# CPU_IO_Ports.net
KiCad netlist of a schematic drawn in Altium Designer
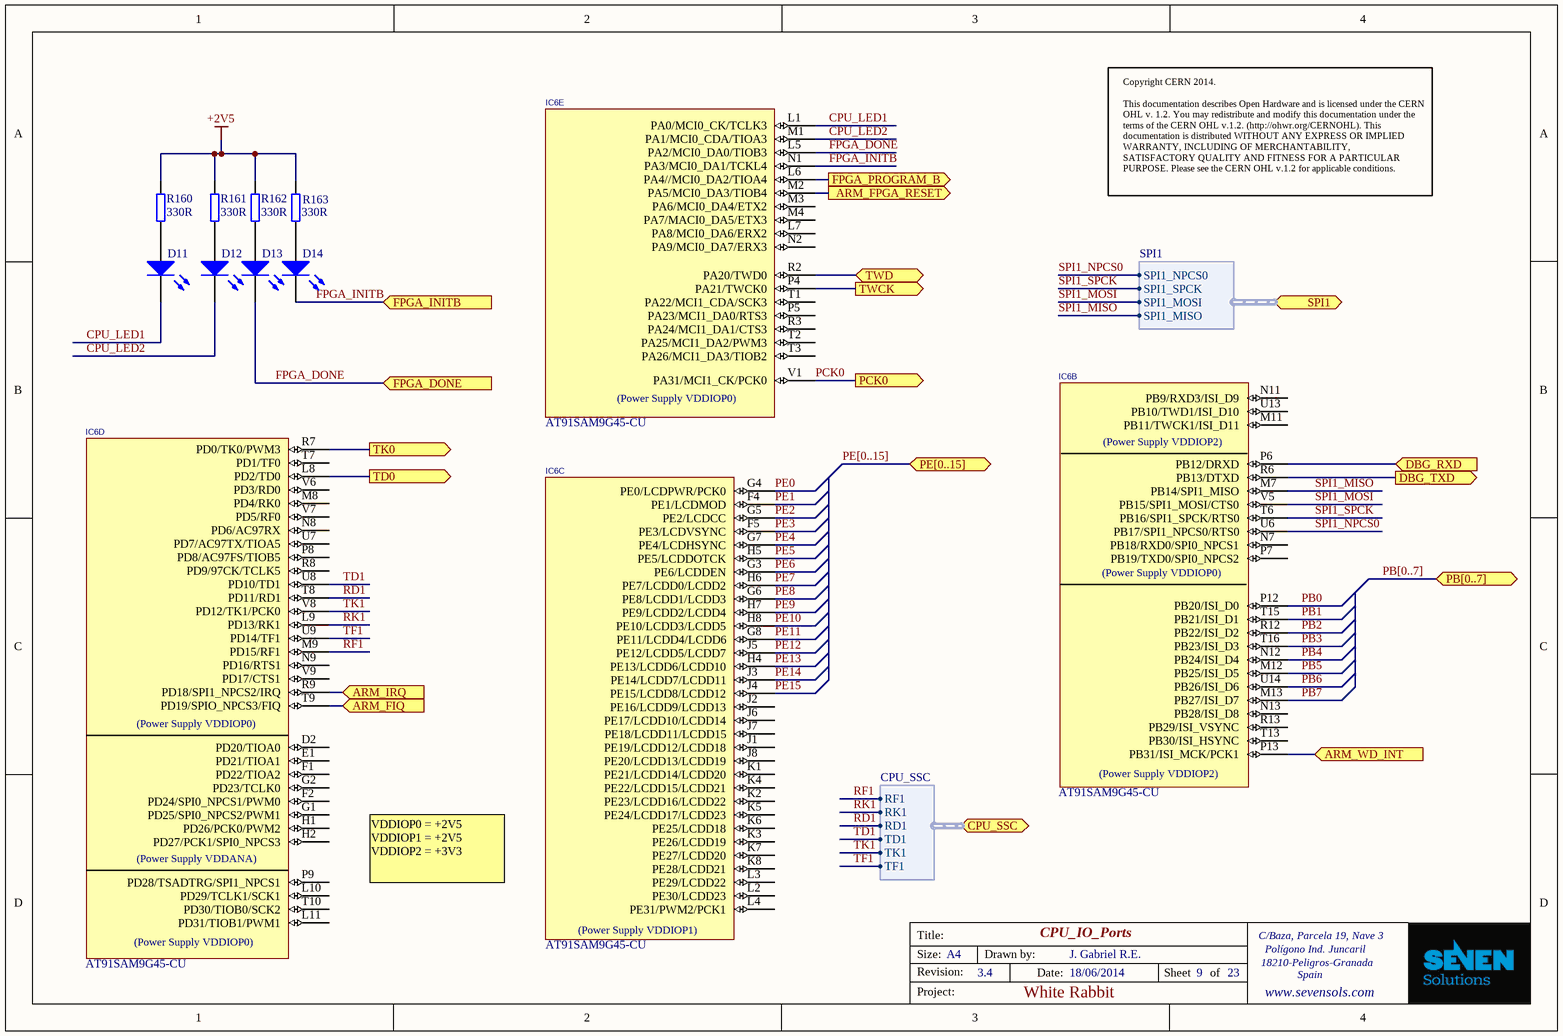
[diagram p0: CPU_IO_Ports.SchDoc]

(export (version "E")
  (design (tool "Eeschema 10.0.6"))
  (components
    (comp (ref "D11")
      (value "LED")
      (footprint "CD1608-0603")
      (description "Typical INFRARED GaAs LED")
      (fields (field (name "PUBLISHER") "Altium Limited"))
      (libsource (lib "wr_switch") (part "LED0"))
    )
    (comp (ref "D12")
      (value "LED")
      (footprint "CD1608-0603")
      (description "Typical INFRARED GaAs LED")
      (fields (field (name "PUBLISHER") "Altium Limited"))
      (libsource (lib "wr_switch") (part "LED0"))
    )
    (comp (ref "D13")
      (value "LED")
      (footprint "CD1608-0603")
      (description "Typical INFRARED GaAs LED")
      (fields (field (name "PUBLISHER") "Altium Limited"))
      (libsource (lib "wr_switch") (part "LED0"))
    )
    (comp (ref "D14")
      (value "LED")
      (footprint "CD1608-0603")
      (description "Typical INFRARED GaAs LED")
      (fields (field (name "PUBLISHER") "Altium Limited"))
      (libsource (lib "wr_switch") (part "LED0"))
    )
    (comp (ref "IC6")
      (value "AT91SAM9G45-CU")
      (footprint "TFBGA324")
      (description "Atmel 400MHz ARM926 MCU")
      (libsource (lib "wr_switch") (part "AT91SAM9G45-CU"))
    )
    (comp (ref "R160")
      (value "330R")
      (footprint "0402")
      (description "SMD Resistor")
      (fields (field (name "TOLERANCE") "±1%"))
      (libsource (lib "wr_switch") (part "RES_SMD"))
    )
    (comp (ref "R161")
      (value "330R")
      (footprint "0402")
      (description "SMD Resistor")
      (fields (field (name "TOLERANCE") "±1%"))
      (libsource (lib "wr_switch") (part "RES_SMD"))
    )
    (comp (ref "R162")
      (value "330R")
      (footprint "0402")
      (description "SMD Resistor")
      (fields (field (name "TOLERANCE") "±1%"))
      (libsource (lib "wr_switch") (part "RES_SMD"))
    )
    (comp (ref "R163")
      (value "330R")
      (footprint "0402")
      (description "SMD Resistor")
      (fields (field (name "TOLERANCE") "±1%"))
      (libsource (lib "wr_switch") (part "RES_SMD"))
    )
  )
  (nets
    (net (code "3") (name "+2V5") (class "Default")
      (node (ref "R160") (pin "2") (pinfunction "2_2") (pintype "passive"))
      (node (ref "R161") (pin "2") (pinfunction "2_2") (pintype "passive"))
      (node (ref "R162") (pin "2") (pinfunction "2_2") (pintype "passive"))
      (node (ref "R163") (pin "2") (pinfunction "2_2") (pintype "passive"))
    )
    (net (code "4") (name "/ARM_FIQ") (class "Default")
      (node (ref "IC6") (pin "T9") (pinfunction "PD19/SPIO_NPCS3/FIQ_T9") (pintype "bidirectional"))
    )
    (net (code "5") (name "/ARM_FPGA_RESET") (class "Default")
      (node (ref "IC6") (pin "M2") (pinfunction "PA5/MCI0_DA3/TIOB4_M2") (pintype "bidirectional"))
    )
    (net (code "6") (name "/ARM_IRQ") (class "Default")
      (node (ref "IC6") (pin "R9") (pinfunction "PD18/SPI1_NPCS2/IRQ_R9") (pintype "bidirectional"))
    )
    (net (code "7") (name "/ARM_WD_INT") (class "Default")
      (node (ref "IC6") (pin "P13") (pinfunction "PB31/ISI_MCK/PCK1_P13") (pintype "bidirectional"))
    )
    (net (code "8") (name "/CPU_LED1") (class "Default")
      (node (ref "D11") (pin "2") (pinfunction "K_2") (pintype "passive"))
      (node (ref "IC6") (pin "L1") (pinfunction "PA0/MCI0_CK/TCLK3_L1") (pintype "bidirectional"))
    )
    (net (code "9") (name "/CPU_LED2") (class "Default")
      (node (ref "D12") (pin "2") (pinfunction "K_2") (pintype "passive"))
      (node (ref "IC6") (pin "M1") (pinfunction "PA1/MCI0_CDA/TIOA3_M1") (pintype "bidirectional"))
    )
    (net (code "10") (name "/DBG_RXD") (class "Default")
      (node (ref "IC6") (pin "P6") (pinfunction "PB12/DRXD_P6") (pintype "bidirectional"))
    )
    (net (code "11") (name "/DBG_TXD") (class "Default")
      (node (ref "IC6") (pin "R6") (pinfunction "PB13/DTXD_R6") (pintype "bidirectional"))
    )
    (net (code "12") (name "/FPGA_DONE") (class "Default")
      (node (ref "D13") (pin "2") (pinfunction "K_2") (pintype "passive"))
      (node (ref "IC6") (pin "L5") (pinfunction "PA2/MCI0_DA0/TIOB3_L5") (pintype "bidirectional"))
    )
    (net (code "13") (name "/FPGA_INITB") (class "Default")
      (node (ref "D14") (pin "2") (pinfunction "K_2") (pintype "passive"))
      (node (ref "IC6") (pin "N1") (pinfunction "PA3/MCI0_DA1/TCKL4_N1") (pintype "bidirectional"))
    )
    (net (code "14") (name "/FPGA_PROGRAM_B") (class "Default")
      (node (ref "IC6") (pin "L6") (pinfunction "PA4//MCI0_DA2/TIOA4_L6") (pintype "bidirectional"))
    )
    (net (code "15") (name "/PB0") (class "Default")
      (node (ref "IC6") (pin "P12") (pinfunction "PB20/ISI_D0_P12") (pintype "bidirectional"))
    )
    (net (code "16") (name "/PB1") (class "Default")
      (node (ref "IC6") (pin "T15") (pinfunction "PB21/ISI_D1_T15") (pintype "bidirectional"))
    )
    (net (code "17") (name "/PB2") (class "Default")
      (node (ref "IC6") (pin "R12") (pinfunction "PB22/ISI_D2_R12") (pintype "bidirectional"))
    )
    (net (code "18") (name "/PB3") (class "Default")
      (node (ref "IC6") (pin "T16") (pinfunction "PB23/ISI_D3_T16") (pintype "bidirectional"))
    )
    (net (code "19") (name "/PB4") (class "Default")
      (node (ref "IC6") (pin "N12") (pinfunction "PB24/ISI_D4_N12") (pintype "bidirectional"))
    )
    (net (code "20") (name "/PB5") (class "Default")
      (node (ref "IC6") (pin "M12") (pinfunction "PB25/ISI_D5_M12") (pintype "bidirectional"))
    )
    (net (code "21") (name "/PB6") (class "Default")
      (node (ref "IC6") (pin "U14") (pinfunction "PB26/ISI_D6_U14") (pintype "bidirectional"))
    )
    (net (code "22") (name "/PB7") (class "Default")
      (node (ref "IC6") (pin "M13") (pinfunction "PB27/ISI_D7_M13") (pintype "bidirectional"))
    )
    (net (code "24") (name "/PCK0") (class "Default")
      (node (ref "IC6") (pin "V1") (pinfunction "PA31/MCI1_CK/PCK0_V1") (pintype "bidirectional"))
    )
    (net (code "25") (name "/PE0") (class "Default")
      (node (ref "IC6") (pin "G4") (pinfunction "PE0/LCDPWR/PCK0_G4") (pintype "bidirectional"))
    )
    (net (code "26") (name "/PE1") (class "Default")
      (node (ref "IC6") (pin "F4") (pinfunction "PE1/LCDMOD_F4") (pintype "bidirectional"))
    )
    (net (code "27") (name "/PE2") (class "Default")
      (node (ref "IC6") (pin "G5") (pinfunction "PE2/LCDCC_G5") (pintype "bidirectional"))
    )
    (net (code "28") (name "/PE3") (class "Default")
      (node (ref "IC6") (pin "F5") (pinfunction "PE3/LCDVSYNC_F5") (pintype "bidirectional"))
    )
    (net (code "29") (name "/PE4") (class "Default")
      (node (ref "IC6") (pin "G7") (pinfunction "PE4/LCDHSYNC_G7") (pintype "bidirectional"))
    )
    (net (code "30") (name "/PE5") (class "Default")
      (node (ref "IC6") (pin "H5") (pinfunction "PE5/LCDDOTCK_H5") (pintype "bidirectional"))
    )
    (net (code "31") (name "/PE6") (class "Default")
      (node (ref "IC6") (pin "G3") (pinfunction "PE6/LCDDEN_G3") (pintype "bidirectional"))
    )
    (net (code "32") (name "/PE7") (class "Default")
      (node (ref "IC6") (pin "H6") (pinfunction "PE7/LCDD0/LCDD2_H6") (pintype "bidirectional"))
    )
    (net (code "33") (name "/PE8") (class "Default")
      (node (ref "IC6") (pin "G6") (pinfunction "PE8/LCDD1/LCDD3_G6") (pintype "bidirectional"))
    )
    (net (code "34") (name "/PE9") (class "Default")
      (node (ref "IC6") (pin "H7") (pinfunction "PE9/LCDD2/LCDD4_H7") (pintype "bidirectional"))
    )
    (net (code "35") (name "/PE10") (class "Default")
      (node (ref "IC6") (pin "H8") (pinfunction "PE10/LCDD3/LCDD5_H8") (pintype "bidirectional"))
    )
    (net (code "36") (name "/PE11") (class "Default")
      (node (ref "IC6") (pin "G8") (pinfunction "PE11/LCDD4/LCDD6_G8") (pintype "bidirectional"))
    )
    (net (code "37") (name "/PE12") (class "Default")
      (node (ref "IC6") (pin "J5") (pinfunction "PE12/LCDD5/LCDD7_J5") (pintype "bidirectional"))
    )
    (net (code "38") (name "/PE13") (class "Default")
      (node (ref "IC6") (pin "H4") (pinfunction "PE13/LCDD6/LCDD10_H4") (pintype "bidirectional"))
    )
    (net (code "39") (name "/PE14") (class "Default")
      (node (ref "IC6") (pin "J3") (pinfunction "PE14/LCDD7/LCDD11_J3") (pintype "bidirectional"))
    )
    (net (code "40") (name "/PE15") (class "Default")
      (node (ref "IC6") (pin "J4") (pinfunction "PE15/LCDD8/LCDD12_J4") (pintype "bidirectional"))
    )
    (net (code "42") (name "/RD1") (class "Default")
      (node (ref "IC6") (pin "T8") (pinfunction "PD11/RD1_T8") (pintype "bidirectional"))
    )
    (net (code "43") (name "/RF1") (class "Default")
      (node (ref "IC6") (pin "M9") (pinfunction "PD15/RF1_M9") (pintype "bidirectional"))
    )
    (net (code "44") (name "/RK1") (class "Default")
      (node (ref "IC6") (pin "L9") (pinfunction "PD13/RK1_L9") (pintype "bidirectional"))
    )
    (net (code "45") (name "/SPI1_MISO") (class "Default")
      (node (ref "IC6") (pin "M7") (pinfunction "PB14/SPI1_MISO_M7") (pintype "bidirectional"))
    )
    (net (code "46") (name "/SPI1_MOSI") (class "Default")
      (node (ref "IC6") (pin "V5") (pinfunction "PB15/SPI1_MOSI/CTS0_V5") (pintype "bidirectional"))
    )
    (net (code "47") (name "/SPI1_NPCS0") (class "Default")
      (node (ref "IC6") (pin "U6") (pinfunction "PB17/SPI1_NPCS0/RTS0_U6") (pintype "bidirectional"))
    )
    (net (code "48") (name "/SPI1_SPCK") (class "Default")
      (node (ref "IC6") (pin "T6") (pinfunction "PB16/SPI1_SPCK/RTS0_T6") (pintype "bidirectional"))
    )
    (net (code "49") (name "/TD0") (class "Default")
      (node (ref "IC6") (pin "L8") (pinfunction "PD2/TD0_L8") (pintype "bidirectional"))
    )
    (net (code "50") (name "/TD1") (class "Default")
      (node (ref "IC6") (pin "U8") (pinfunction "PD10/TD1_U8") (pintype "bidirectional"))
    )
    (net (code "51") (name "/TF1") (class "Default")
      (node (ref "IC6") (pin "U9") (pinfunction "PD14/TF1_U9") (pintype "bidirectional"))
    )
    (net (code "52") (name "/TK0") (class "Default")
      (node (ref "IC6") (pin "R7") (pinfunction "PD0/TK0/PWM3_R7") (pintype "bidirectional"))
    )
    (net (code "53") (name "/TK1") (class "Default")
      (node (ref "IC6") (pin "V8") (pinfunction "PD12/TK1/PCK0_V8") (pintype "bidirectional"))
    )
    (net (code "54") (name "/TWCK") (class "Default")
      (node (ref "IC6") (pin "P4") (pinfunction "PA21/TWCK0_P4") (pintype "bidirectional"))
    )
    (net (code "55") (name "/TWD") (class "Default")
      (node (ref "IC6") (pin "R2") (pinfunction "PA20/TWD0_R2") (pintype "bidirectional"))
    )
    (net (code "58") (name "Net-(D11-A)") (class "Default")
      (node (ref "D11") (pin "1") (pinfunction "A_1") (pintype "passive"))
      (node (ref "R160") (pin "1") (pinfunction "1_1") (pintype "passive"))
    )
    (net (code "59") (name "Net-(D12-A)") (class "Default")
      (node (ref "D12") (pin "1") (pinfunction "A_1") (pintype "passive"))
      (node (ref "R161") (pin "1") (pinfunction "1_1") (pintype "passive"))
    )
    (net (code "60") (name "Net-(D13-A)") (class "Default")
      (node (ref "D13") (pin "1") (pinfunction "A_1") (pintype "passive"))
      (node (ref "R162") (pin "1") (pinfunction "1_1") (pintype "passive"))
    )
    (net (code "61") (name "Net-(D14-A)") (class "Default")
      (node (ref "D14") (pin "1") (pinfunction "A_1") (pintype "passive"))
      (node (ref "R163") (pin "1") (pinfunction "1_1") (pintype "passive"))
    )
    (net (code "62") (name "unconnected-(IC6B-PB9{slash}RXD3{slash}ISI_D9-PadN11)") (class "Default")
      (node (ref "IC6") (pin "N11") (pinfunction "PB9/RXD3/ISI_D9_N11") (pintype "bidirectional"))
    )
    (net (code "63") (name "unconnected-(IC6B-PB10{slash}TWD1{slash}ISI_D10-PadU13)") (class "Default")
      (node (ref "IC6") (pin "U13") (pinfunction "PB10/TWD1/ISI_D10_U13") (pintype "bidirectional"))
    )
    (net (code "64") (name "unconnected-(IC6B-PB11{slash}TWCK1{slash}ISI_D11-PadM11)") (class "Default")
      (node (ref "IC6") (pin "M11") (pinfunction "PB11/TWCK1/ISI_D11_M11") (pintype "bidirectional"))
    )
    (net (code "65") (name "unconnected-(IC6B-PB18{slash}RXD0{slash}SPI0_NPCS1-PadN7)") (class "Default")
      (node (ref "IC6") (pin "N7") (pinfunction "PB18/RXD0/SPI0_NPCS1_N7") (pintype "bidirectional"))
    )
    (net (code "66") (name "unconnected-(IC6B-PB19{slash}TXD0{slash}SPI0_NPCS2-PadP7)") (class "Default")
      (node (ref "IC6") (pin "P7") (pinfunction "PB19/TXD0/SPI0_NPCS2_P7") (pintype "bidirectional"))
    )
    (net (code "67") (name "unconnected-(IC6B-PB28{slash}ISI_D8-PadN13)") (class "Default")
      (node (ref "IC6") (pin "N13") (pinfunction "PB28/ISI_D8_N13") (pintype "bidirectional"))
    )
    (net (code "68") (name "unconnected-(IC6B-PB29{slash}ISI_VSYNC-PadR13)") (class "Default")
      (node (ref "IC6") (pin "R13") (pinfunction "PB29/ISI_VSYNC_R13") (pintype "bidirectional"))
    )
    (net (code "69") (name "unconnected-(IC6B-PB30{slash}ISI_HSYNC-PadT13)") (class "Default")
      (node (ref "IC6") (pin "T13") (pinfunction "PB30/ISI_HSYNC_T13") (pintype "bidirectional"))
    )
    (net (code "70") (name "unconnected-(IC6C-PE16{slash}LCDD9{slash}LCDD13-PadJ2)") (class "Default")
      (node (ref "IC6") (pin "J2") (pinfunction "PE16/LCDD9/LCDD13_J2") (pintype "bidirectional"))
    )
    (net (code "71") (name "unconnected-(IC6C-PE17{slash}LCDD10{slash}LCDD14-PadJ6)") (class "Default")
      (node (ref "IC6") (pin "J6") (pinfunction "PE17/LCDD10/LCDD14_J6") (pintype "bidirectional"))
    )
    (net (code "72") (name "unconnected-(IC6C-PE18{slash}LCDD11{slash}LCDD15-PadJ7)") (class "Default")
      (node (ref "IC6") (pin "J7") (pinfunction "PE18/LCDD11/LCDD15_J7") (pintype "bidirectional"))
    )
    (net (code "73") (name "unconnected-(IC6C-PE19{slash}LCDD12{slash}LCDD18-PadJ1)") (class "Default")
      (node (ref "IC6") (pin "J1") (pinfunction "PE19/LCDD12/LCDD18_J1") (pintype "bidirectional"))
    )
    (net (code "74") (name "unconnected-(IC6C-PE20{slash}LCDD13{slash}LCDD19-PadJ8)") (class "Default")
      (node (ref "IC6") (pin "J8") (pinfunction "PE20/LCDD13/LCDD19_J8") (pintype "bidirectional"))
    )
    (net (code "75") (name "unconnected-(IC6C-PE21{slash}LCDD14{slash}LCDD20-PadK1)") (class "Default")
      (node (ref "IC6") (pin "K1") (pinfunction "PE21/LCDD14/LCDD20_K1") (pintype "bidirectional"))
    )
    (net (code "76") (name "unconnected-(IC6C-PE22{slash}LCDD15{slash}LCDD21-PadK4)") (class "Default")
      (node (ref "IC6") (pin "K4") (pinfunction "PE22/LCDD15/LCDD21_K4") (pintype "bidirectional"))
    )
    (net (code "77") (name "unconnected-(IC6C-PE23{slash}LCDD16{slash}LCDD22-PadK2)") (class "Default")
      (node (ref "IC6") (pin "K2") (pinfunction "PE23/LCDD16/LCDD22_K2") (pintype "bidirectional"))
    )
    (net (code "78") (name "unconnected-(IC6C-PE24{slash}LCDD17{slash}LCDD23-PadK5)") (class "Default")
      (node (ref "IC6") (pin "K5") (pinfunction "PE24/LCDD17/LCDD23_K5") (pintype "bidirectional"))
    )
    (net (code "79") (name "unconnected-(IC6C-PE25{slash}LCDD18-PadK6)") (class "Default")
      (node (ref "IC6") (pin "K6") (pinfunction "PE25/LCDD18_K6") (pintype "bidirectional"))
    )
    (net (code "80") (name "unconnected-(IC6C-PE26{slash}LCDD19-PadK3)") (class "Default")
      (node (ref "IC6") (pin "K3") (pinfunction "PE26/LCDD19_K3") (pintype "bidirectional"))
    )
    (net (code "81") (name "unconnected-(IC6C-PE27{slash}LCDD20-PadK7)") (class "Default")
      (node (ref "IC6") (pin "K7") (pinfunction "PE27/LCDD20_K7") (pintype "bidirectional"))
    )
    (net (code "82") (name "unconnected-(IC6C-PE28{slash}LCDD21-PadK8)") (class "Default")
      (node (ref "IC6") (pin "K8") (pinfunction "PE28/LCDD21_K8") (pintype "bidirectional"))
    )
    (net (code "83") (name "unconnected-(IC6C-PE29{slash}LCDD22-PadL3)") (class "Default")
      (node (ref "IC6") (pin "L3") (pinfunction "PE29/LCDD22_L3") (pintype "bidirectional"))
    )
    (net (code "84") (name "unconnected-(IC6C-PE30{slash}LCDD23-PadL2)") (class "Default")
      (node (ref "IC6") (pin "L2") (pinfunction "PE30/LCDD23_L2") (pintype "bidirectional"))
    )
    (net (code "85") (name "unconnected-(IC6C-PE31{slash}PWM2{slash}PCK1-PadL4)") (class "Default")
      (node (ref "IC6") (pin "L4") (pinfunction "PE31/PWM2/PCK1_L4") (pintype "bidirectional"))
    )
    (net (code "86") (name "unconnected-(IC6D-PD1{slash}TF0-PadT7)") (class "Default")
      (node (ref "IC6") (pin "T7") (pinfunction "PD1/TF0_T7") (pintype "bidirectional"))
    )
    (net (code "87") (name "unconnected-(IC6D-PD3{slash}RD0-PadV6)") (class "Default")
      (node (ref "IC6") (pin "V6") (pinfunction "PD3/RD0_V6") (pintype "bidirectional"))
    )
    (net (code "88") (name "unconnected-(IC6D-PD4{slash}RK0-PadM8)") (class "Default")
      (node (ref "IC6") (pin "M8") (pinfunction "PD4/RK0_M8") (pintype "bidirectional"))
    )
    (net (code "89") (name "unconnected-(IC6D-PD5{slash}RF0-PadV7)") (class "Default")
      (node (ref "IC6") (pin "V7") (pinfunction "PD5/RF0_V7") (pintype "bidirectional"))
    )
    (net (code "90") (name "unconnected-(IC6D-PD6{slash}AC97RX-PadN8)") (class "Default")
      (node (ref "IC6") (pin "N8") (pinfunction "PD6/AC97RX_N8") (pintype "bidirectional"))
    )
    (net (code "91") (name "unconnected-(IC6D-PD7{slash}AC97TX{slash}TIOA5-PadU7)") (class "Default")
      (node (ref "IC6") (pin "U7") (pinfunction "PD7/AC97TX/TIOA5_U7") (pintype "bidirectional"))
    )
    (net (code "92") (name "unconnected-(IC6D-PD8{slash}AC97FS{slash}TIOB5-PadP8)") (class "Default")
      (node (ref "IC6") (pin "P8") (pinfunction "PD8/AC97FS/TIOB5_P8") (pintype "bidirectional"))
    )
    (net (code "93") (name "unconnected-(IC6D-PD9{slash}97CK{slash}TCLK5-PadR8)") (class "Default")
      (node (ref "IC6") (pin "R8") (pinfunction "PD9/97CK/TCLK5_R8") (pintype "bidirectional"))
    )
    (net (code "94") (name "unconnected-(IC6D-PD16{slash}RTS1-PadN9)") (class "Default")
      (node (ref "IC6") (pin "N9") (pinfunction "PD16/RTS1_N9") (pintype "bidirectional"))
    )
    (net (code "95") (name "unconnected-(IC6D-PD17{slash}CTS1-PadV9)") (class "Default")
      (node (ref "IC6") (pin "V9") (pinfunction "PD17/CTS1_V9") (pintype "bidirectional"))
    )
    (net (code "96") (name "unconnected-(IC6D-PD20{slash}TIOA0-PadD2)") (class "Default")
      (node (ref "IC6") (pin "D2") (pinfunction "PD20/TIOA0_D2") (pintype "bidirectional"))
    )
    (net (code "97") (name "unconnected-(IC6D-PD21{slash}TIOA1-PadE1)") (class "Default")
      (node (ref "IC6") (pin "E1") (pinfunction "PD21/TIOA1_E1") (pintype "bidirectional"))
    )
    (net (code "98") (name "unconnected-(IC6D-PD22{slash}TIOA2-PadF1)") (class "Default")
      (node (ref "IC6") (pin "F1") (pinfunction "PD22/TIOA2_F1") (pintype "bidirectional"))
    )
    (net (code "99") (name "unconnected-(IC6D-PD23{slash}TCLK0-PadG2)") (class "Default")
      (node (ref "IC6") (pin "G2") (pinfunction "PD23/TCLK0_G2") (pintype "bidirectional"))
    )
    (net (code "100") (name "unconnected-(IC6D-PD24{slash}SPI0_NPCS1{slash}PWM0-PadF2)") (class "Default")
      (node (ref "IC6") (pin "F2") (pinfunction "PD24/SPI0_NPCS1/PWM0_F2") (pintype "bidirectional"))
    )
    (net (code "101") (name "unconnected-(IC6D-PD25{slash}SPI0_NPCS2{slash}PWM1-PadG1)") (class "Default")
      (node (ref "IC6") (pin "G1") (pinfunction "PD25/SPI0_NPCS2/PWM1_G1") (pintype "bidirectional"))
    )
    (net (code "102") (name "unconnected-(IC6D-PD26{slash}PCK0{slash}PWM2-PadH1)") (class "Default")
      (node (ref "IC6") (pin "H1") (pinfunction "PD26/PCK0/PWM2_H1") (pintype "bidirectional"))
    )
    (net (code "103") (name "unconnected-(IC6D-PD27{slash}PCK1{slash}SPI0_NPCS3-PadH2)") (class "Default")
      (node (ref "IC6") (pin "H2") (pinfunction "PD27/PCK1/SPI0_NPCS3_H2") (pintype "bidirectional"))
    )
    (net (code "104") (name "unconnected-(IC6D-PD28{slash}TSADTRG{slash}SPI1_NPCS1-PadP9)") (class "Default")
      (node (ref "IC6") (pin "P9") (pinfunction "PD28/TSADTRG/SPI1_NPCS1_P9") (pintype "bidirectional"))
    )
    (net (code "105") (name "unconnected-(IC6D-PD29{slash}TCLK1{slash}SCK1-PadL10)") (class "Default")
      (node (ref "IC6") (pin "L10") (pinfunction "PD29/TCLK1/SCK1_L10") (pintype "bidirectional"))
    )
    (net (code "106") (name "unconnected-(IC6D-PD30{slash}TIOB0{slash}SCK2-PadT10)") (class "Default")
      (node (ref "IC6") (pin "T10") (pinfunction "PD30/TIOB0/SCK2_T10") (pintype "bidirectional"))
    )
    (net (code "107") (name "unconnected-(IC6D-PD31{slash}TIOB1{slash}PWM1-PadL11)") (class "Default")
      (node (ref "IC6") (pin "L11") (pinfunction "PD31/TIOB1/PWM1_L11") (pintype "bidirectional"))
    )
    (net (code "108") (name "unconnected-(IC6E-PA6{slash}MCI0_DA4{slash}ETX2-PadM3)") (class "Default")
      (node (ref "IC6") (pin "M3") (pinfunction "PA6/MCI0_DA4/ETX2_M3") (pintype "bidirectional"))
    )
    (net (code "109") (name "unconnected-(IC6E-PA7{slash}MACI0_DA5{slash}ETX3-PadM4)") (class "Default")
      (node (ref "IC6") (pin "M4") (pinfunction "PA7/MACI0_DA5/ETX3_M4") (pintype "bidirectional"))
    )
    (net (code "110") (name "unconnected-(IC6E-PA8{slash}MCI0_DA6{slash}ERX2-PadL7)") (class "Default")
      (node (ref "IC6") (pin "L7") (pinfunction "PA8/MCI0_DA6/ERX2_L7") (pintype "bidirectional"))
    )
    (net (code "111") (name "unconnected-(IC6E-PA9{slash}MCI0_DA7{slash}ERX3-PadN2)") (class "Default")
      (node (ref "IC6") (pin "N2") (pinfunction "PA9/MCI0_DA7/ERX3_N2") (pintype "bidirectional"))
    )
    (net (code "112") (name "unconnected-(IC6E-PA22{slash}MCI1_CDA{slash}SCK3-PadT1)") (class "Default")
      (node (ref "IC6") (pin "T1") (pinfunction "PA22/MCI1_CDA/SCK3_T1") (pintype "bidirectional"))
    )
    (net (code "113") (name "unconnected-(IC6E-PA23{slash}MCI1_DA0{slash}RTS3-PadP5)") (class "Default")
      (node (ref "IC6") (pin "P5") (pinfunction "PA23/MCI1_DA0/RTS3_P5") (pintype "bidirectional"))
    )
    (net (code "114") (name "unconnected-(IC6E-PA24{slash}MCI1_DA1{slash}CTS3-PadR3)") (class "Default")
      (node (ref "IC6") (pin "R3") (pinfunction "PA24/MCI1_DA1/CTS3_R3") (pintype "bidirectional"))
    )
    (net (code "115") (name "unconnected-(IC6E-PA25{slash}MCI1_DA2{slash}PWM3-PadT2)") (class "Default")
      (node (ref "IC6") (pin "T2") (pinfunction "PA25/MCI1_DA2/PWM3_T2") (pintype "bidirectional"))
    )
    (net (code "116") (name "unconnected-(IC6E-PA26{slash}MCI1_DA3{slash}TIOB2-PadT3)") (class "Default")
      (node (ref "IC6") (pin "T3") (pinfunction "PA26/MCI1_DA3/TIOB2_T3") (pintype "bidirectional"))
    )
  )
)
